# reset_circuit.net
KiCad netlist of a schematic drawn in EAGLE
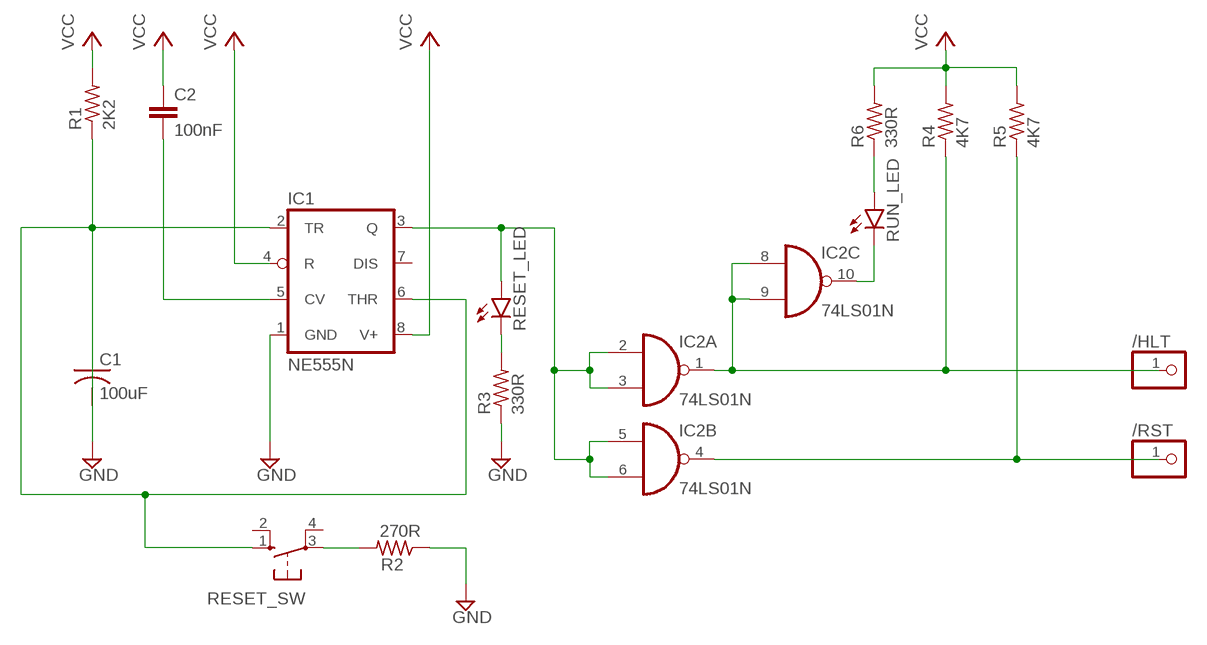
[diagram p0: schematic, sheet 1]

(export (version "E")
  (design (tool "Eeschema 10.0.6"))
  (components
    (comp (ref "/HLT")
      (value "PINHD-1X1")
      (footprint "eagle-import:1X01")
      (libsource (lib "eagle-import") (part "PINHD-1X1"))
    )
    (comp (ref "/RST")
      (value "PINHD-1X1")
      (footprint "eagle-import:1X01")
      (libsource (lib "eagle-import") (part "PINHD-1X1"))
    )
    (comp (ref "C1")
      (value "100uF")
      (footprint "eagle-import:C025-025X050")
      (libsource (lib "eagle-import") (part "C-US025-025X050"))
    )
    (comp (ref "C2")
      (value "100nF")
      (footprint "eagle-import:C2.5-3")
      (libsource (lib "eagle-import") (part "C2,5-3"))
    )
    (comp (ref "IC1")
      (value "NE555N")
      (footprint "eagle-import:DIL08")
      (libsource (lib "eagle-import") (part "555NNE"))
    )
    (comp (ref "IC2")
      (value "74LS01N")
      (footprint "eagle-import:DIL14")
      (libsource (lib "eagle-import") (part "7401NLS"))
    )
    (comp (ref "R1")
      (value "2K2")
      (footprint "eagle-import:0204_7")
      (libsource (lib "eagle-import") (part "R-US_0204/7"))
    )
    (comp (ref "R2")
      (value "270R")
      (footprint "eagle-import:0204_7")
      (libsource (lib "eagle-import") (part "R-US_0204/7"))
    )
    (comp (ref "R3")
      (value "330R")
      (footprint "eagle-import:0204_7")
      (libsource (lib "eagle-import") (part "R-US_0204/7"))
    )
    (comp (ref "R4")
      (value "4K7")
      (footprint "eagle-import:0204_7")
      (libsource (lib "eagle-import") (part "R-US_0204/7"))
    )
    (comp (ref "R5")
      (value "4K7")
      (footprint "eagle-import:0204_7")
      (libsource (lib "eagle-import") (part "R-US_0204/7"))
    )
    (comp (ref "R6")
      (value "330R")
      (footprint "eagle-import:0204_7")
      (libsource (lib "eagle-import") (part "R-US_0204/7"))
    )
    (comp (ref "RESET_LED")
      (value "LED5MM")
      (footprint "eagle-import:LED5MM")
      (libsource (lib "eagle-import") (part "LED5MM"))
    )
    (comp (ref "RESET_SW")
      (value "10-XX")
      (footprint "eagle-import:B3F-10XX")
      (fields (field (name "MPN") "B3F-1000"))
      (libsource (lib "eagle-import") (part "10-XX"))
    )
    (comp (ref "RUN_LED")
      (value "LED5MM")
      (footprint "eagle-import:LED5MM")
      (libsource (lib "eagle-import") (part "LED5MM"))
    )
  )
  (nets
    (net (code "1") (name "GND") (class "Default")
      (node (ref "C1") (pin "1") (pinfunction "1_1") (pintype "passive"))
      (node (ref "IC1") (pin "1") (pinfunction "GND_1") (pintype "power_in"))
      (node (ref "R2") (pin "1") (pinfunction "1_1") (pintype "passive"))
      (node (ref "R3") (pin "1") (pinfunction "1_1") (pintype "passive"))
    )
    (net (code "2") (name "Net-(IC1-CV)") (class "Default")
      (node (ref "C2") (pin "2") (pinfunction "2_2") (pintype "passive"))
      (node (ref "IC1") (pin "5") (pinfunction "CV_5") (pintype "input"))
    )
    (net (code "3") (name "Net-(IC1-Q)") (class "Default")
      (node (ref "IC1") (pin "3") (pinfunction "Q_3") (pintype "output"))
      (node (ref "IC2") (pin "2") (pinfunction "I0_2") (pintype "input"))
      (node (ref "IC2") (pin "3") (pinfunction "I1_3") (pintype "input"))
      (node (ref "IC2") (pin "5") (pinfunction "I0_5") (pintype "input"))
      (node (ref "IC2") (pin "6") (pinfunction "I1_6") (pintype "input"))
      (node (ref "RESET_LED") (pin "A") (pinfunction "A_A") (pintype "passive"))
    )
    (net (code "4") (name "Net-(IC1-THR)") (class "Default")
      (node (ref "C1") (pin "2") (pinfunction "2_2") (pintype "passive"))
      (node (ref "IC1") (pin "2") (pinfunction "TR_2") (pintype "input"))
      (node (ref "IC1") (pin "6") (pinfunction "THR_6") (pintype "input"))
      (node (ref "R1") (pin "1") (pinfunction "1_1") (pintype "passive"))
      (node (ref "RESET_SW") (pin "1") (pinfunction "S_1") (pintype "passive"))
    )
    (net (code "5") (name "Net-(IC2A-O)") (class "Default")
      (node (ref "/HLT") (pin "1") (pinfunction "1_1") (pintype "passive"))
      (node (ref "IC2") (pin "1") (pinfunction "O_1") (pintype "open_collector"))
      (node (ref "IC2") (pin "8") (pinfunction "I0_8") (pintype "input"))
      (node (ref "IC2") (pin "9") (pinfunction "I1_9") (pintype "input"))
      (node (ref "R4") (pin "1") (pinfunction "1_1") (pintype "passive"))
    )
    (net (code "6") (name "Net-(IC2B-O)") (class "Default")
      (node (ref "/RST") (pin "1") (pinfunction "1_1") (pintype "passive"))
      (node (ref "IC2") (pin "4") (pinfunction "O_4") (pintype "open_collector"))
      (node (ref "R5") (pin "1") (pinfunction "1_1") (pintype "passive"))
    )
    (net (code "7") (name "Net-(IC2C-O)") (class "Default")
      (node (ref "IC2") (pin "10") (pinfunction "O_10") (pintype "open_collector"))
      (node (ref "RUN_LED") (pin "K") (pinfunction "C_K") (pintype "passive"))
    )
    (net (code "8") (name "Net-(R6-Pad1)") (class "Default")
      (node (ref "R6") (pin "1") (pinfunction "1_1") (pintype "passive"))
      (node (ref "RUN_LED") (pin "A") (pinfunction "A_A") (pintype "passive"))
    )
    (net (code "9") (name "Net-(RESET_LED-C)") (class "Default")
      (node (ref "R3") (pin "2") (pinfunction "2_2") (pintype "passive"))
      (node (ref "RESET_LED") (pin "K") (pinfunction "C_K") (pintype "passive"))
    )
    (net (code "10") (name "Net-(RESET_SW-P)") (class "Default")
      (node (ref "R2") (pin "2") (pinfunction "2_2") (pintype "passive"))
      (node (ref "RESET_SW") (pin "3") (pinfunction "P_3") (pintype "passive"))
    )
    (net (code "11") (name "VCC") (class "Default")
      (node (ref "C2") (pin "1") (pinfunction "1_1") (pintype "passive"))
      (node (ref "IC1") (pin "4") (pinfunction "R_4") (pintype "input"))
      (node (ref "IC1") (pin "8") (pinfunction "V+_8") (pintype "power_in"))
      (node (ref "R1") (pin "2") (pinfunction "2_2") (pintype "passive"))
      (node (ref "R4") (pin "2") (pinfunction "2_2") (pintype "passive"))
      (node (ref "R5") (pin "2") (pinfunction "2_2") (pintype "passive"))
      (node (ref "R6") (pin "2") (pinfunction "2_2") (pintype "passive"))
    )
    (net (code "12") (name "unconnected-(IC1-DIS-Pad7)") (class "Default")
      (node (ref "IC1") (pin "7") (pinfunction "DIS_7") (pintype "input"))
    )
    (net (code "13") (name "unconnected-(RESET_SW-P1-Pad4)") (class "Default")
      (node (ref "RESET_SW") (pin "4") (pinfunction "P1_4") (pintype "passive"))
    )
    (net (code "14") (name "unconnected-(RESET_SW-S1-Pad2)") (class "Default")
      (node (ref "RESET_SW") (pin "2") (pinfunction "S1_2") (pintype "passive"))
    )
  )
)
